# cc2530.net
KiCad netlist of a schematic drawn in Altium Designer
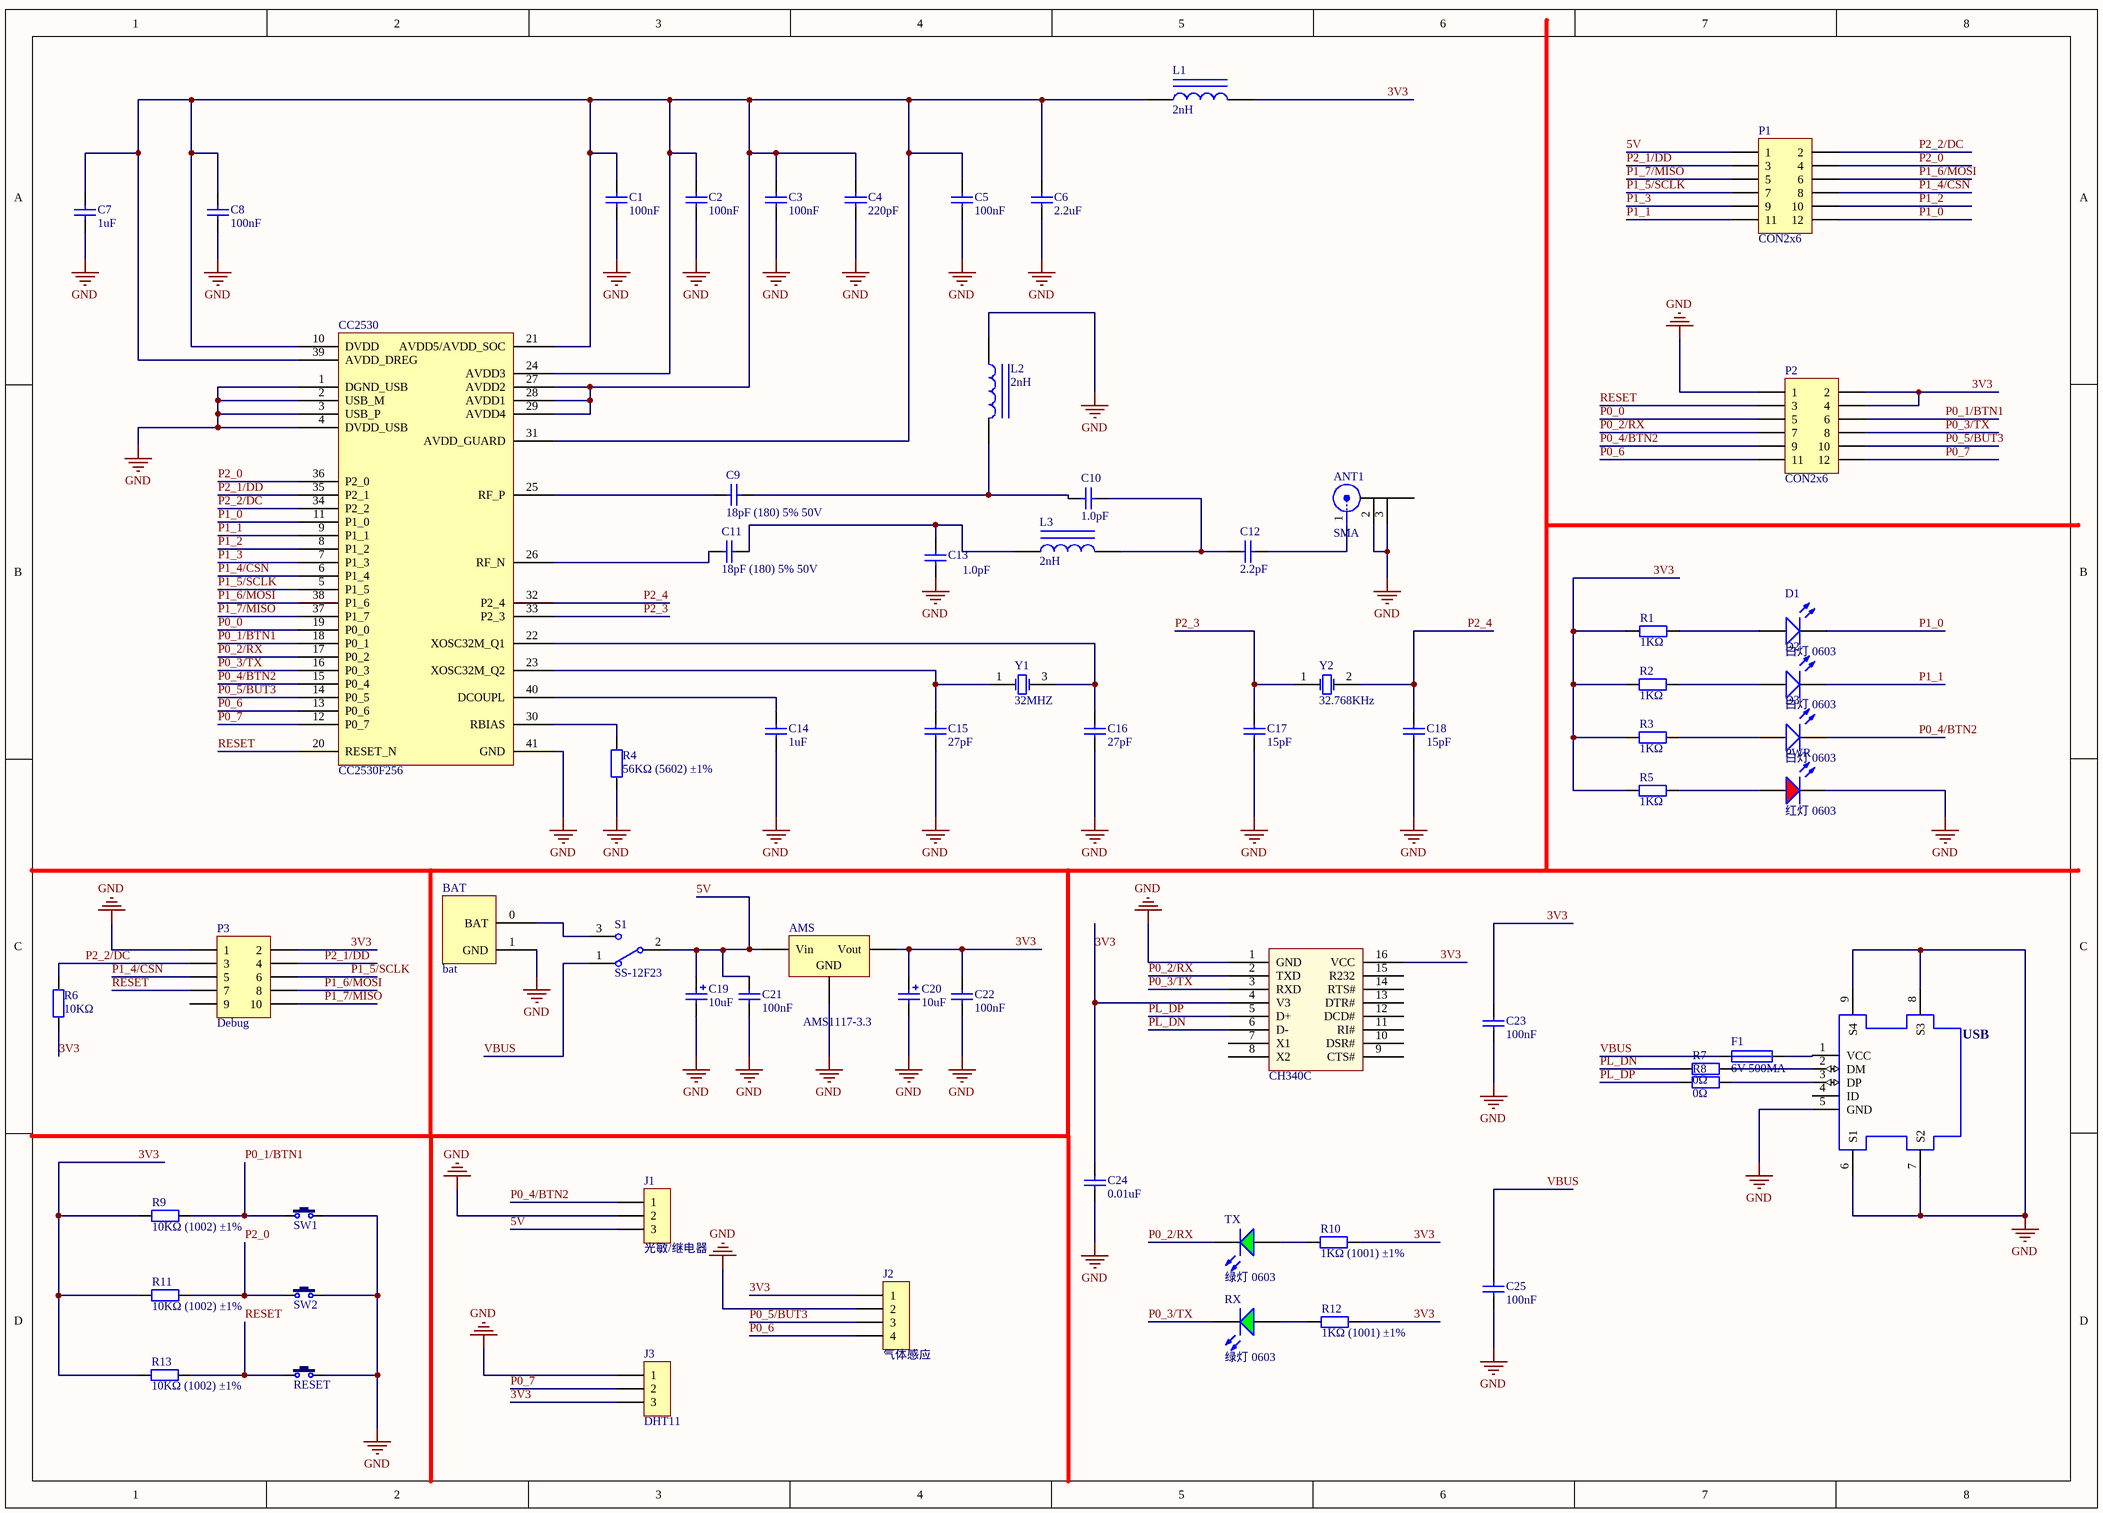
[diagram p0: cc2530.SchDoc]

(export (version "E")
  (design (tool "Eeschema 10.0.6"))
  (components
    (comp (ref "AMS")
      (value "AMS1117-3.3")
      (footprint "SOT-223")
      (description "低压差线性稳压(LDO)")
      (libsource (lib "Miscellaneous Devices LC") (part "SOT-223 AMS1117-3.3"))
    )
    (comp (ref "ANT1") (value "SMA") (footprint "SMA-KE") (libsource (lib "2530核心板原理图库") (part "SMA")))
    (comp (ref "BAT") (value "bat") (footprint "BAT") (libsource (lib "2530底板原理图库") (part "bat")))
    (comp (ref "C1")
      (value "100nF")
      (footprint "0603_C")
      (description "贴片电容")
      (libsource (lib "Miscellaneous Devices LC") (part "0603 100nF (104) 10% 50V"))
    )
    (comp (ref "C2")
      (value "100nF")
      (footprint "0603_C")
      (description "贴片电容")
      (libsource (lib "Miscellaneous Devices LC") (part "0603 100nF (104) 10% 50V"))
    )
    (comp (ref "C3")
      (value "100nF")
      (footprint "0603_C")
      (description "贴片电容")
      (libsource (lib "Miscellaneous Devices LC") (part "0603 100nF (104) 10% 50V"))
    )
    (comp (ref "C4")
      (value "220pF")
      (footprint "0603_C")
      (description "贴片电容")
      (libsource (lib "Miscellaneous Devices LC") (part "0603 220pF (221) 10% 50V"))
    )
    (comp (ref "C5")
      (value "100nF")
      (footprint "0603_C")
      (description "贴片电容")
      (libsource (lib "Miscellaneous Devices LC") (part "0603 100nF (104) 10% 50V"))
    )
    (comp (ref "C6")
      (value "2.2uF")
      (footprint "0603_C")
      (description "贴片电容")
      (libsource (lib "Miscellaneous Devices LC") (part "0603 2.2uF (225) 10% 16V"))
    )
    (comp (ref "C7")
      (value "1uF")
      (footprint "0603_C")
      (description "贴片电容")
      (libsource (lib "Miscellaneous Devices LC") (part "0603 1uF (105) 10% 50V"))
    )
    (comp (ref "C8")
      (value "100nF")
      (footprint "0603_C")
      (description "贴片电容")
      (libsource (lib "Miscellaneous Devices LC") (part "0603 100nF (104) 10% 50V"))
    )
    (comp (ref "C9")
      (value "18pF (180) 5% 50V")
      (footprint "0603_C")
      (description "贴片电容")
      (libsource (lib "Miscellaneous Devices LC") (part "0603 18pF (180) 5% 50V"))
    )
    (comp (ref "C10")
      (value "1.0pF")
      (footprint "0805_C")
      (description "贴片电容")
      (libsource (lib "Miscellaneous Devices LC") (part "0805 1.0pF (010) 0.25pF 50V"))
    )
    (comp (ref "C11")
      (value "18pF (180) 5% 50V")
      (footprint "0603_C")
      (description "贴片电容")
      (libsource (lib "Miscellaneous Devices LC") (part "0603 18pF (180) 5% 50V"))
    )
    (comp (ref "C12")
      (value "2.2pF")
      (footprint "0603_C")
      (description "贴片电容")
      (libsource (lib "Miscellaneous Devices LC") (part "0603 2.2uF (225) 10% 16V"))
    )
    (comp (ref "C13")
      (value "1.0pF")
      (footprint "0805_C")
      (description "贴片电容")
      (libsource (lib "Miscellaneous Devices LC") (part "0805 1.0pF (010) 0.25pF 50V"))
    )
    (comp (ref "C14")
      (value "1uF")
      (footprint "0603_C")
      (description "贴片电容")
      (libsource (lib "Miscellaneous Devices LC") (part "0603 100nF (104) 10% 50V"))
    )
    (comp (ref "C15")
      (value "27pF")
      (footprint "0603_C")
      (description "贴片电容")
      (libsource (lib "Miscellaneous Devices LC") (part "0603 100nF (104) 10% 50V"))
    )
    (comp (ref "C16")
      (value "27pF")
      (footprint "0603_C")
      (description "贴片电容")
      (libsource (lib "Miscellaneous Devices LC") (part "0603 100nF (104) 10% 50V"))
    )
    (comp (ref "C17")
      (value "15pF")
      (footprint "0603_C")
      (description "贴片电容")
      (libsource (lib "Miscellaneous Devices LC") (part "0603 100nF (104) 10% 50V"))
    )
    (comp (ref "C18")
      (value "15pF")
      (footprint "0603_C")
      (description "贴片电容")
      (libsource (lib "Miscellaneous Devices LC") (part "0603 100nF (104) 10% 50V"))
    )
    (comp (ref "C19")
      (value "10uF")
      (footprint "CASE-A_3216")
      (description "钽电容")
      (libsource (lib "Miscellaneous Devices LC") (part "3216 10uF (106) 10% 16V"))
    )
    (comp (ref "C20")
      (value "10uF")
      (footprint "CASE-A_3216")
      (description "钽电容")
      (libsource (lib "Miscellaneous Devices LC") (part "3216 10uF (106) 10% 16V"))
    )
    (comp (ref "C21")
      (value "100nF")
      (footprint "0603_C")
      (description "贴片电容")
      (libsource (lib "Miscellaneous Devices LC") (part "0603 100nF (104) 10% 50V"))
    )
    (comp (ref "C22")
      (value "100nF")
      (footprint "0603_C")
      (description "贴片电容")
      (libsource (lib "Miscellaneous Devices LC") (part "0603 100nF (104) 10% 50V"))
    )
    (comp (ref "C23")
      (value "100nF")
      (footprint "0603_C")
      (description "贴片电容")
      (libsource (lib "Miscellaneous Devices LC") (part "0603 100nF (104) 10% 50V"))
    )
    (comp (ref "C24")
      (value "0.01uF")
      (footprint "0603_C")
      (description "贴片电容")
      (libsource (lib "Miscellaneous Devices LC") (part "0603 100nF (104) 10% 50V"))
    )
    (comp (ref "C25")
      (value "100nF")
      (footprint "0603_C")
      (description "贴片电容")
      (libsource (lib "Miscellaneous Devices LC") (part "0603 100nF (104) 10% 50V"))
    )
    (comp (ref "CC2530")
      (value "CC2530F256")
      (footprint "PVQFN-N40")
      (libsource (lib "2530核心板原理图库") (part "CC2530"))
    )
    (comp (ref "CH340C")
      (value "CH340C")
      (footprint "SOIC-16_150mil")
      (libsource (lib "1.9 - CH340系列编程器芯片") (part "CH340C"))
    )
    (comp (ref "D1")
      (value "白灯 0603")
      (footprint "0603_LED_S1")
      (description "发光二极管")
      (libsource (lib "Miscellaneous Devices LC") (part "0603 白灯"))
    )
    (comp (ref "D2")
      (value "白灯 0603")
      (footprint "0603_LED_S1")
      (description "发光二极管")
      (libsource (lib "Miscellaneous Devices LC") (part "0603 白灯"))
    )
    (comp (ref "D3")
      (value "白灯 0603")
      (footprint "0603_LED_S1")
      (description "发光二极管")
      (libsource (lib "Miscellaneous Devices LC") (part "0603 白灯"))
    )
    (comp (ref "F1")
      (value "6V 500MA")
      (footprint "0805")
      (description "保险丝")
      (libsource (lib "Component") (part "FUSE"))
    )
    (comp (ref "J1")
      (value "光敏/继电器")
      (footprint "HDR1X3")
      (description "连接器")
      (libsource (lib "Connector") (part "CON3"))
    )
    (comp (ref "J2")
      (value "气体感应")
      (footprint "HDR1X4")
      (description "连接器")
      (libsource (lib "Connector") (part "CON4"))
    )
    (comp (ref "J3")
      (value "DHT11")
      (footprint "HDR1X3")
      (description "连接器")
      (libsource (lib "Connector") (part "CON3"))
    )
    (comp (ref "L1")
      (value "2nH")
      (footprint "0402_L")
      (description "贴片电感")
      (libsource (lib "Miscellaneous Devices LC") (part "0402 2.7nH 0.3nH"))
    )
    (comp (ref "L2")
      (value "2nH")
      (footprint "0402_L")
      (description "贴片电感")
      (libsource (lib "Miscellaneous Devices LC") (part "0402 2.7nH 0.3nH"))
    )
    (comp (ref "L3")
      (value "2nH")
      (footprint "0402_L")
      (description "贴片电感")
      (libsource (lib "Miscellaneous Devices LC") (part "0402 2.7nH 0.3nH"))
    )
    (comp (ref "P1")
      (value "CON2x6")
      (footprint "2530底板PCB库:CON2X6")
      (libsource (lib "2530底板原理图库") (part "CON2x6"))
    )
    (comp (ref "P2")
      (value "CON2x6")
      (footprint "2530底板PCB库:CON2X6")
      (libsource (lib "2530底板原理图库") (part "CON2x6"))
    )
    (comp (ref "P3")
      (value "Debug")
      (footprint "DEBUG10")
      (description "Header, 5-Pin, Dual row")
      (libsource (lib "2530底板原理图库") (part "Header 5X2"))
    )
    (comp (ref "PWR")
      (value "红灯 0603")
      (footprint "0603_LED_S1")
      (description "发光二极管")
      (libsource (lib "Miscellaneous Devices LC") (part "0603 红灯"))
    )
    (comp (ref "R1")
      (value "1KΩ")
      (footprint "0603_R")
      (description "贴片电阻")
      (libsource (lib "Miscellaneous Devices LC") (part "0603 1.1KΩ (1101) 1%"))
    )
    (comp (ref "R2")
      (value "1KΩ")
      (footprint "0603_R")
      (description "贴片电阻")
      (libsource (lib "Miscellaneous Devices LC") (part "0603 1.1KΩ (1101) 1%"))
    )
    (comp (ref "R3")
      (value "1KΩ")
      (footprint "0603_R")
      (description "贴片电阻")
      (libsource (lib "Miscellaneous Devices LC") (part "0603 1.1KΩ (1101) 1%"))
    )
    (comp (ref "R4")
      (value "56KΩ (5602) ±1%")
      (footprint "0603_R")
      (description "贴片电阻")
      (libsource (lib "Miscellaneous Devices LC") (part "0603 56KΩ (5602) 1%"))
    )
    (comp (ref "R5")
      (value "1KΩ")
      (footprint "0603_R")
      (description "贴片电阻")
      (libsource (lib "Miscellaneous Devices LC") (part "0603 1.1KΩ (1101) 1%"))
    )
    (comp (ref "R6")
      (value "10KΩ")
      (footprint "0603_R")
      (description "贴片电阻")
      (libsource (lib "") (part "0603 10KΩ (1002) 1%_1"))
    )
    (comp (ref "R7")
      (value "0Ω")
      (footprint "0603_R")
      (description "贴片电阻")
      (libsource (lib "Miscellaneous Devices LC") (part "0603 0Ω (0R0) 1%"))
    )
    (comp (ref "R8")
      (value "0Ω")
      (footprint "0603_R")
      (description "贴片电阻")
      (libsource (lib "Miscellaneous Devices LC") (part "0603 0Ω (0R0) 1%"))
    )
    (comp (ref "R9")
      (value "10KΩ (1002) ±1%")
      (footprint "0603_R")
      (description "贴片电阻")
      (libsource (lib "Miscellaneous Devices LC") (part "0603 10KΩ (1002) 1%"))
    )
    (comp (ref "R10")
      (value "1KΩ (1001) ±1%")
      (footprint "0603_R")
      (description "贴片电阻")
      (libsource (lib "Miscellaneous Devices LC") (part "0603 1KΩ (1001) 1%"))
    )
    (comp (ref "R11")
      (value "10KΩ (1002) ±1%")
      (footprint "0603_R")
      (description "贴片电阻")
      (libsource (lib "Miscellaneous Devices LC") (part "0603 10KΩ (1002) 1%"))
    )
    (comp (ref "R12")
      (value "1KΩ (1001) ±1%")
      (footprint "0603_R")
      (description "贴片电阻")
      (libsource (lib "Miscellaneous Devices LC") (part "0603 1KΩ (1001) 1%"))
    )
    (comp (ref "R13")
      (value "10KΩ (1002) ±1%")
      (footprint "0603_R")
      (description "贴片电阻")
      (libsource (lib "Miscellaneous Devices LC") (part "0603 10KΩ (1002) 1%"))
    )
    (comp (ref "RESET")
      (value "6x6x5")
      (footprint "TSW SMD-3*6*2.5")
      (description "侧按直插6x6轻触开关")
      (fields (field (name "版权归属") "封装库来自淘宝 ID：黄晶宝石"))
      (libsource (lib "0.7 - 常用按键-开关") (part "TSW DIP-6x6_V"))
    )
    (comp (ref "RX")
      (value "绿灯 0603")
      (footprint "0603_LED_S1")
      (description "发光二极管")
      (libsource (lib "Miscellaneous Devices LC") (part "0603 绿灯"))
    )
    (comp (ref "S1")
      (value "SS-12F23")
      (footprint "SS-12F23")
      (description "1路波动开关")
      (fields (field (name "版权归属") "封装库来自淘宝 ID：黄晶宝石"))
      (libsource (lib "0.7 - 常用按键-开关") (part "SSW-1P"))
    )
    (comp (ref "SW1")
      (value "6x6x5")
      (footprint "TSW SMD-3*6*2.5")
      (description "侧按直插6x6轻触开关")
      (fields (field (name "版权归属") "封装库来自淘宝 ID：黄晶宝石"))
      (libsource (lib "0.7 - 常用按键-开关") (part "TSW DIP-6x6_V"))
    )
    (comp (ref "SW2")
      (value "6x6x5")
      (footprint "TSW SMD-3*6*2.5")
      (description "侧按直插6x6轻触开关")
      (fields (field (name "版权归属") "封装库来自淘宝 ID：黄晶宝石"))
      (libsource (lib "0.7 - 常用按键-开关") (part "TSW DIP-6x6_V"))
    )
    (comp (ref "TX")
      (value "绿灯 0603")
      (footprint "0603_LED_S1")
      (description "发光二极管")
      (libsource (lib "Miscellaneous Devices LC") (part "0603 绿灯"))
    )
    (comp (ref "USB")
      (value "Mini USB")
      (footprint "SMT-MINI USB")
      (description "IC")
      (fields
        (field (name "MANUFACTURER PART NUMBER") "USB Plug P/N: MUSB-B5-S-VT-02")
        (field (name "PUBLISHER1") "Stephen Lui")
        (field (name "PUBLISHER2") "Tianshen")
      )
      (libsource (lib "2530底板原理图库") (part "USB-1"))
    )
    (comp (ref "Y1")
      (value "32MHZ")
      (footprint "SMD-3225_4P")
      (description "贴片晶振")
      (libsource (lib "Miscellaneous Devices LC") (part "SMD-3225_4P  25MHZ 12PF 10PPM"))
    )
    (comp (ref "Y2")
      (value "32.768KHz")
      (footprint "SMD-3215_2P FC - 135")
      (description "贴片晶振")
      (libsource (lib "Miscellaneous Devices LC") (part "SMD-3215_2P 32.768KHz 20ppm 12.5pF"))
    )
  )
  (nets
    (net (code "1") (name "/3V3") (class "Default")
      (node (ref "AMS") (pin "2") (pinfunction "Vout_2") (pintype "passive"))
      (node (ref "C20") (pin "1") (pinfunction "1_1") (pintype "passive"))
      (node (ref "C22") (pin "2") (pinfunction "2_2") (pintype "passive"))
      (node (ref "C23") (pin "2") (pinfunction "2_2") (pintype "passive"))
      (node (ref "C24") (pin "2") (pinfunction "2_2") (pintype "passive"))
      (node (ref "CH340C") (pin "16") (pinfunction "VCC_16") (pintype "passive"))
      (node (ref "CH340C") (pin "4") (pinfunction "V3_4") (pintype "passive"))
      (node (ref "J2") (pin "1") (pinfunction "1_1") (pintype "passive"))
      (node (ref "J3") (pin "3") (pinfunction "3_3") (pintype "passive"))
      (node (ref "L1") (pin "2") (pinfunction "2_2") (pintype "passive"))
      (node (ref "P2") (pin "2") (pinfunction "2_2") (pintype "passive"))
      (node (ref "P2") (pin "4") (pinfunction "4_4") (pintype "passive"))
      (node (ref "P3") (pin "2") (pinfunction "2_2") (pintype "passive"))
      (node (ref "R1") (pin "1") (pinfunction "1_1") (pintype "passive"))
      (node (ref "R10") (pin "2") (pinfunction "2_2") (pintype "passive"))
      (node (ref "R11") (pin "1") (pinfunction "1_1") (pintype "passive"))
      (node (ref "R12") (pin "2") (pinfunction "2_2") (pintype "passive"))
      (node (ref "R13") (pin "1") (pinfunction "1_1") (pintype "passive"))
      (node (ref "R2") (pin "1") (pinfunction "1_1") (pintype "passive"))
      (node (ref "R3") (pin "1") (pinfunction "1_1") (pintype "passive"))
      (node (ref "R5") (pin "1") (pinfunction "1_1") (pintype "passive"))
      (node (ref "R6") (pin "1") (pinfunction "1_1") (pintype "passive"))
      (node (ref "R9") (pin "1") (pinfunction "1_1") (pintype "passive"))
    )
    (net (code "2") (name "/5V") (class "Default")
      (node (ref "AMS") (pin "3") (pinfunction "Vin_3") (pintype "passive"))
      (node (ref "C19") (pin "1") (pinfunction "1_1") (pintype "passive"))
      (node (ref "C21") (pin "2") (pinfunction "2_2") (pintype "passive"))
      (node (ref "J1") (pin "3") (pinfunction "3_3") (pintype "passive"))
      (node (ref "P1") (pin "1") (pinfunction "1_1") (pintype "passive"))
      (node (ref "S1") (pin "2") (pinfunction "2_2") (pintype "passive"))
    )
    (net (code "3") (name "/P0_0") (class "Default")
      (node (ref "CC2530") (pin "19") (pinfunction "P0_0_19") (pintype "passive"))
      (node (ref "P2") (pin "5") (pinfunction "5_5") (pintype "passive"))
    )
    (net (code "4") (name "/P0_1{slash}BTN1") (class "Default")
      (node (ref "CC2530") (pin "18") (pinfunction "P0_1_18") (pintype "passive"))
      (node (ref "P2") (pin "6") (pinfunction "6_6") (pintype "passive"))
      (node (ref "R9") (pin "2") (pinfunction "2_2") (pintype "passive"))
      (node (ref "SW1") (pin "1") (pinfunction "1_1") (pintype "passive"))
    )
    (net (code "5") (name "/P0_2{slash}RX") (class "Default")
      (node (ref "CC2530") (pin "17") (pinfunction "P0_2_17") (pintype "passive"))
      (node (ref "CH340C") (pin "2") (pinfunction "TXD_2") (pintype "passive"))
      (node (ref "P2") (pin "7") (pinfunction "7_7") (pintype "passive"))
      (node (ref "TX") (pin "K") (pinfunction "K_K") (pintype "passive"))
    )
    (net (code "6") (name "/P0_3{slash}TX") (class "Default")
      (node (ref "CC2530") (pin "16") (pinfunction "P0_3_16") (pintype "passive"))
      (node (ref "CH340C") (pin "3") (pinfunction "RXD_3") (pintype "passive"))
      (node (ref "P2") (pin "8") (pinfunction "8_8") (pintype "passive"))
      (node (ref "RX") (pin "K") (pinfunction "K_K") (pintype "passive"))
    )
    (net (code "7") (name "/P0_4{slash}BTN2") (class "Default")
      (node (ref "CC2530") (pin "15") (pinfunction "P0_4_15") (pintype "passive"))
      (node (ref "D3") (pin "K") (pinfunction "K_K") (pintype "passive"))
      (node (ref "J1") (pin "1") (pinfunction "1_1") (pintype "passive"))
      (node (ref "P2") (pin "9") (pinfunction "9_9") (pintype "passive"))
    )
    (net (code "8") (name "/P0_5{slash}BUT3") (class "Default")
      (node (ref "CC2530") (pin "14") (pinfunction "P0_5_14") (pintype "passive"))
      (node (ref "J2") (pin "3") (pinfunction "3_3") (pintype "passive"))
      (node (ref "P2") (pin "10") (pinfunction "10_10") (pintype "passive"))
    )
    (net (code "9") (name "/P0_6") (class "Default")
      (node (ref "CC2530") (pin "13") (pinfunction "P0_6_13") (pintype "passive"))
      (node (ref "J2") (pin "4") (pinfunction "4_4") (pintype "passive"))
      (node (ref "P2") (pin "11") (pinfunction "11_11") (pintype "passive"))
    )
    (net (code "10") (name "/P0_7") (class "Default")
      (node (ref "CC2530") (pin "12") (pinfunction "P0_7_12") (pintype "passive"))
      (node (ref "J3") (pin "2") (pinfunction "2_2") (pintype "passive"))
      (node (ref "P2") (pin "12") (pinfunction "12_12") (pintype "passive"))
    )
    (net (code "11") (name "/P1_0") (class "Default")
      (node (ref "CC2530") (pin "11") (pinfunction "P1_0_11") (pintype "passive"))
      (node (ref "D1") (pin "K") (pinfunction "K_K") (pintype "passive"))
      (node (ref "P1") (pin "12") (pinfunction "12_12") (pintype "passive"))
    )
    (net (code "12") (name "/P1_1") (class "Default")
      (node (ref "CC2530") (pin "9") (pinfunction "P1_1_9") (pintype "passive"))
      (node (ref "D2") (pin "K") (pinfunction "K_K") (pintype "passive"))
      (node (ref "P1") (pin "11") (pinfunction "11_11") (pintype "passive"))
    )
    (net (code "13") (name "/P1_2") (class "Default")
      (node (ref "CC2530") (pin "8") (pinfunction "P1_2_8") (pintype "passive"))
      (node (ref "P1") (pin "10") (pinfunction "10_10") (pintype "passive"))
    )
    (net (code "14") (name "/P1_3") (class "Default")
      (node (ref "CC2530") (pin "7") (pinfunction "P1_3_7") (pintype "passive"))
      (node (ref "P1") (pin "9") (pinfunction "9_9") (pintype "passive"))
    )
    (net (code "15") (name "/P1_4{slash}CSN") (class "Default")
      (node (ref "CC2530") (pin "6") (pinfunction "P1_4_6") (pintype "passive"))
      (node (ref "P1") (pin "8") (pinfunction "8_8") (pintype "passive"))
      (node (ref "P3") (pin "5") (pinfunction "5_5") (pintype "passive"))
    )
    (net (code "16") (name "/P1_5{slash}SCLK") (class "Default")
      (node (ref "CC2530") (pin "5") (pinfunction "P1_5_5") (pintype "passive"))
      (node (ref "P1") (pin "7") (pinfunction "7_7") (pintype "passive"))
      (node (ref "P3") (pin "6") (pinfunction "6_6") (pintype "passive"))
    )
    (net (code "17") (name "/P1_6{slash}MOSI") (class "Default")
      (node (ref "CC2530") (pin "38") (pinfunction "P1_6_38") (pintype "passive"))
      (node (ref "P1") (pin "6") (pinfunction "6_6") (pintype "passive"))
      (node (ref "P3") (pin "8") (pinfunction "8_8") (pintype "passive"))
    )
    (net (code "18") (name "/P1_7{slash}MISO") (class "Default")
      (node (ref "CC2530") (pin "37") (pinfunction "P1_7_37") (pintype "passive"))
      (node (ref "P1") (pin "5") (pinfunction "5_5") (pintype "passive"))
      (node (ref "P3") (pin "10") (pinfunction "10_10") (pintype "passive"))
    )
    (net (code "19") (name "/P2_0") (class "Default")
      (node (ref "CC2530") (pin "36") (pinfunction "P2_0_36") (pintype "passive"))
      (node (ref "P1") (pin "4") (pinfunction "4_4") (pintype "passive"))
      (node (ref "R11") (pin "2") (pinfunction "2_2") (pintype "passive"))
      (node (ref "SW2") (pin "1") (pinfunction "1_1") (pintype "passive"))
    )
    (net (code "20") (name "/P2_1{slash}DD") (class "Default")
      (node (ref "CC2530") (pin "35") (pinfunction "P2_1_35") (pintype "passive"))
      (node (ref "P1") (pin "3") (pinfunction "3_3") (pintype "passive"))
      (node (ref "P3") (pin "4") (pinfunction "4_4") (pintype "passive"))
    )
    (net (code "21") (name "/P2_2{slash}DC") (class "Default")
      (node (ref "CC2530") (pin "34") (pinfunction "P2_2_34") (pintype "passive"))
      (node (ref "P1") (pin "2") (pinfunction "2_2") (pintype "passive"))
      (node (ref "P3") (pin "3") (pinfunction "3_3") (pintype "passive"))
      (node (ref "R6") (pin "2") (pinfunction "2_2") (pintype "passive"))
    )
    (net (code "22") (name "/P2_3") (class "Default")
      (node (ref "C17") (pin "2") (pinfunction "2_2") (pintype "passive"))
      (node (ref "CC2530") (pin "33") (pinfunction "P2_3_33") (pintype "passive"))
      (node (ref "Y2") (pin "1") (pinfunction "OSC1_1") (pintype "passive"))
    )
    (net (code "23") (name "/P2_4") (class "Default")
      (node (ref "C18") (pin "2") (pinfunction "2_2") (pintype "passive"))
      (node (ref "CC2530") (pin "32") (pinfunction "P2_4_32") (pintype "passive"))
      (node (ref "Y2") (pin "2") (pinfunction "OSC2_2") (pintype "passive"))
    )
    (net (code "24") (name "/PL_DN") (class "Default")
      (node (ref "CH340C") (pin "6") (pinfunction "D-_6") (pintype "passive"))
      (node (ref "R7") (pin "1") (pinfunction "1_1") (pintype "passive"))
    )
    (net (code "25") (name "/PL_DP") (class "Default")
      (node (ref "CH340C") (pin "5") (pinfunction "D+_5") (pintype "passive"))
      (node (ref "R8") (pin "1") (pinfunction "1_1") (pintype "passive"))
    )
    (net (code "26") (name "/RESET") (class "Default")
      (node (ref "CC2530") (pin "20") (pinfunction "RESET_N_20") (pintype "passive"))
      (node (ref "P2") (pin "3") (pinfunction "3_3") (pintype "passive"))
      (node (ref "P3") (pin "7") (pinfunction "7_7") (pintype "passive"))
      (node (ref "R13") (pin "2") (pinfunction "2_2") (pintype "passive"))
      (node (ref "RESET") (pin "1") (pinfunction "1_1") (pintype "passive"))
    )
    (net (code "27") (name "/VBUS") (class "Default")
      (node (ref "C25") (pin "2") (pinfunction "2_2") (pintype "passive"))
      (node (ref "F1") (pin "1") (pinfunction "1_1") (pintype "passive"))
      (node (ref "S1") (pin "1") (pinfunction "1_1") (pintype "passive"))
    )
    (net (code "28") (name "GND") (class "Default")
      (node (ref "AMS") (pin "1") (pinfunction "GND_1") (pintype "passive"))
      (node (ref "ANT1") (pin "2") (pinfunction "2_2") (pintype "passive"))
      (node (ref "ANT1") (pin "3") (pinfunction "3_3") (pintype "passive"))
      (node (ref "BAT") (pin "1") (pinfunction "GND_1") (pintype "passive"))
      (node (ref "C1") (pin "1") (pinfunction "1_1") (pintype "passive"))
      (node (ref "C13") (pin "1") (pinfunction "1_1") (pintype "passive"))
      (node (ref "C14") (pin "1") (pinfunction "1_1") (pintype "passive"))
      (node (ref "C15") (pin "1") (pinfunction "1_1") (pintype "passive"))
      (node (ref "C16") (pin "1") (pinfunction "1_1") (pintype "passive"))
      (node (ref "C17") (pin "1") (pinfunction "1_1") (pintype "passive"))
      (node (ref "C18") (pin "1") (pinfunction "1_1") (pintype "passive"))
      (node (ref "C19") (pin "2") (pinfunction "2_2") (pintype "passive"))
      (node (ref "C2") (pin "1") (pinfunction "1_1") (pintype "passive"))
      (node (ref "C20") (pin "2") (pinfunction "2_2") (pintype "passive"))
      (node (ref "C21") (pin "1") (pinfunction "1_1") (pintype "passive"))
      (node (ref "C22") (pin "1") (pinfunction "1_1") (pintype "passive"))
      (node (ref "C23") (pin "1") (pinfunction "1_1") (pintype "passive"))
      (node (ref "C24") (pin "1") (pinfunction "1_1") (pintype "passive"))
      (node (ref "C25") (pin "1") (pinfunction "1_1") (pintype "passive"))
      (node (ref "C3") (pin "1") (pinfunction "1_1") (pintype "passive"))
      (node (ref "C4") (pin "1") (pinfunction "1_1") (pintype "passive"))
      (node (ref "C5") (pin "1") (pinfunction "1_1") (pintype "passive"))
      (node (ref "C6") (pin "1") (pinfunction "1_1") (pintype "passive"))
      (node (ref "C7") (pin "1") (pinfunction "1_1") (pintype "passive"))
      (node (ref "C8") (pin "1") (pinfunction "1_1") (pintype "passive"))
      (node (ref "CC2530") (pin "1") (pinfunction "DGND_USB_1") (pintype "passive"))
      (node (ref "CC2530") (pin "2") (pinfunction "USB_M_2") (pintype "passive"))
      (node (ref "CC2530") (pin "3") (pinfunction "USB_P_3") (pintype "passive"))
      (node (ref "CC2530") (pin "4") (pinfunction "DVDD_USB_4") (pintype "passive"))
      (node (ref "CC2530") (pin "41") (pinfunction "GND_41") (pintype "passive"))
      (node (ref "CH340C") (pin "1") (pinfunction "GND_1") (pintype "passive"))
      (node (ref "J1") (pin "2") (pinfunction "2_2") (pintype "passive"))
      (node (ref "J2") (pin "2") (pinfunction "2_2") (pintype "passive"))
      (node (ref "J3") (pin "1") (pinfunction "1_1") (pintype "passive"))
      (node (ref "L2") (pin "1") (pinfunction "1_1") (pintype "passive"))
      (node (ref "P2") (pin "1") (pinfunction "1_1") (pintype "passive"))
      (node (ref "P3") (pin "1") (pinfunction "1_1") (pintype "passive"))
      (node (ref "PWR") (pin "K") (pinfunction "K_K") (pintype "passive"))
      (node (ref "R4") (pin "1") (pinfunction "1_1") (pintype "passive"))
      (node (ref "RESET") (pin "2") (pinfunction "2_2") (pintype "passive"))
      (node (ref "SW1") (pin "2") (pinfunction "2_2") (pintype "passive"))
      (node (ref "SW2") (pin "2") (pinfunction "2_2") (pintype "passive"))
      (node (ref "USB") (pin "5") (pinfunction "GND_5") (pintype "passive"))
      (node (ref "USB") (pin "6") (pinfunction "S1_6") (pintype "passive"))
      (node (ref "USB") (pin "7") (pinfunction "S2_7") (pintype "passive"))
      (node (ref "USB") (pin "8") (pinfunction "S3_8") (pintype "passive"))
      (node (ref "USB") (pin "9") (pinfunction "S4_9") (pintype "passive"))
    )
    (net (code "29") (name "Net-(ANT1-Pad1)") (class "Default")
      (node (ref "ANT1") (pin "1") (pinfunction "1_1") (pintype "passive"))
      (node (ref "C12") (pin "2") (pinfunction "2_2") (pintype "passive"))
    )
    (net (code "30") (name "Net-(BAT-BAT)") (class "Default")
      (node (ref "BAT") (pin "0") (pinfunction "BAT_0") (pintype "passive"))
      (node (ref "S1") (pin "3") (pinfunction "3_3") (pintype "passive"))
    )
    (net (code "31") (name "Net-(C10-Pad1)") (class "Default")
      (node (ref "C10") (pin "1") (pinfunction "1_1") (pintype "passive"))
      (node (ref "C9") (pin "2") (pinfunction "2_2") (pintype "passive"))
      (node (ref "L2") (pin "2") (pinfunction "2_2") (pintype "passive"))
    )
    (net (code "32") (name "Net-(C10-Pad2)") (class "Default")
      (node (ref "C10") (pin "2") (pinfunction "2_2") (pintype "passive"))
      (node (ref "C12") (pin "1") (pinfunction "1_1") (pintype "passive"))
      (node (ref "L3") (pin "2") (pinfunction "2_2") (pintype "passive"))
    )
    (net (code "33") (name "Net-(C11-Pad2)") (class "Default")
      (node (ref "C11") (pin "2") (pinfunction "2_2") (pintype "passive"))
      (node (ref "C13") (pin "2") (pinfunction "2_2") (pintype "passive"))
      (node (ref "L3") (pin "1") (pinfunction "1_1") (pintype "passive"))
    )
    (net (code "34") (name "Net-(CC2530-AVDD1)") (class "Default")
      (node (ref "C1") (pin "2") (pinfunction "2_2") (pintype "passive"))
      (node (ref "C2") (pin "2") (pinfunction "2_2") (pintype "passive"))
      (node (ref "C3") (pin "2") (pinfunction "2_2") (pintype "passive"))
      (node (ref "C4") (pin "2") (pinfunction "2_2") (pintype "passive"))
      (node (ref "C5") (pin "2") (pinfunction "2_2") (pintype "passive"))
      (node (ref "C6") (pin "2") (pinfunction "2_2") (pintype "passive"))
      (node (ref "C7") (pin "2") (pinfunction "2_2") (pintype "passive"))
      (node (ref "C8") (pin "2") (pinfunction "2_2") (pintype "passive"))
      (node (ref "CC2530") (pin "10") (pinfunction "DVDD_10") (pintype "passive"))
      (node (ref "CC2530") (pin "21") (pinfunction "AVDD5/AVDD_SOC_21") (pintype "passive"))
      (node (ref "CC2530") (pin "24") (pinfunction "AVDD3_24") (pintype "passive"))
      (node (ref "CC2530") (pin "27") (pinfunction "AVDD2_27") (pintype "passive"))
      (node (ref "CC2530") (pin "28") (pinfunction "AVDD1_28") (pintype "passive"))
      (node (ref "CC2530") (pin "29") (pinfunction "AVDD4_29") (pintype "passive"))
      (node (ref "CC2530") (pin "31") (pinfunction "AVDD_GUARD_31") (pintype "passive"))
      (node (ref "CC2530") (pin "39") (pinfunction "AVDD_DREG_39") (pintype "passive"))
      (node (ref "L1") (pin "1") (pinfunction "1_1") (pintype "passive"))
    )
    (net (code "35") (name "Net-(CC2530-DCOUPL)") (class "Default")
      (node (ref "C14") (pin "2") (pinfunction "2_2") (pintype "passive"))
      (node (ref "CC2530") (pin "40") (pinfunction "DCOUPL_40") (pintype "passive"))
    )
    (net (code "36") (name "Net-(CC2530-RBIAS)") (class "Default")
      (node (ref "CC2530") (pin "30") (pinfunction "RBIAS_30") (pintype "passive"))
      (node (ref "R4") (pin "2") (pinfunction "2_2") (pintype "passive"))
    )
    (net (code "37") (name "Net-(CC2530-RF_N)") (class "Default")
      (node (ref "C11") (pin "1") (pinfunction "1_1") (pintype "passive"))
      (node (ref "CC2530") (pin "26") (pinfunction "RF_N_26") (pintype "passive"))
    )
    (net (code "38") (name "Net-(CC2530-RF_P)") (class "Default")
      (node (ref "C9") (pin "1") (pinfunction "1_1") (pintype "passive"))
      (node (ref "CC2530") (pin "25") (pinfunction "RF_P_25") (pintype "passive"))
    )
    (net (code "39") (name "Net-(CC2530-XOSC32M_Q1)") (class "Default")
      (node (ref "C16") (pin "2") (pinfunction "2_2") (pintype "passive"))
      (node (ref "CC2530") (pin "22") (pinfunction "XOSC32M_Q1_22") (pintype "passive"))
      (node (ref "Y1") (pin "3") (pinfunction "OSC2_3") (pintype "passive"))
    )
    (net (code "40") (name "Net-(CC2530-XOSC32M_Q2)") (class "Default")
      (node (ref "C15") (pin "2") (pinfunction "2_2") (pintype "passive"))
      (node (ref "CC2530") (pin "23") (pinfunction "XOSC32M_Q2_23") (pintype "passive"))
      (node (ref "Y1") (pin "1") (pinfunction "OSC1_1") (pintype "passive"))
    )
    (net (code "41") (name "Net-(D1-PadA)") (class "Default")
      (node (ref "D1") (pin "A") (pinfunction "A_A") (pintype "passive"))
      (node (ref "R1") (pin "2") (pinfunction "2_2") (pintype "passive"))
    )
    (net (code "42") (name "Net-(D2-PadA)") (class "Default")
      (node (ref "D2") (pin "A") (pinfunction "A_A") (pintype "passive"))
      (node (ref "R2") (pin "2") (pinfunction "2_2") (pintype "passive"))
    )
    (net (code "43") (name "Net-(D3-PadA)") (class "Default")
      (node (ref "D3") (pin "A") (pinfunction "A_A") (pintype "passive"))
      (node (ref "R3") (pin "2") (pinfunction "2_2") (pintype "passive"))
    )
    (net (code "44") (name "Net-(PWR-PadA)") (class "Default")
      (node (ref "PWR") (pin "A") (pinfunction "A_A") (pintype "passive"))
      (node (ref "R5") (pin "2") (pinfunction "2_2") (pintype "passive"))
    )
    (net (code "45") (name "Net-(R10-Pad1)") (class "Default")
      (node (ref "R10") (pin "1") (pinfunction "1_1") (pintype "passive"))
      (node (ref "TX") (pin "A") (pinfunction "A_A") (pintype "passive"))
    )
    (net (code "46") (name "Net-(R12-Pad1)") (class "Default")
      (node (ref "R12") (pin "1") (pinfunction "1_1") (pintype "passive"))
      (node (ref "RX") (pin "A") (pinfunction "A_A") (pintype "passive"))
    )
    (net (code "47") (name "Net-(USB-DM)") (class "Default")
      (node (ref "R7") (pin "2") (pinfunction "2_2") (pintype "passive"))
      (node (ref "USB") (pin "2") (pinfunction "DM_2") (pintype "bidirectional"))
    )
    (net (code "48") (name "Net-(USB-DP)") (class "Default")
      (node (ref "R8") (pin "2") (pinfunction "2_2") (pintype "passive"))
      (node (ref "USB") (pin "3") (pinfunction "DP_3") (pintype "bidirectional"))
    )
    (net (code "49") (name "Net-(USB-VCC)") (class "Default")
      (node (ref "F1") (pin "2") (pinfunction "2_2") (pintype "passive"))
      (node (ref "USB") (pin "1") (pinfunction "VCC_1") (pintype "passive"))
    )
    (net (code "50") (name "unconnected-(CH340C-CTS#-Pad9)") (class "Default")
      (node (ref "CH340C") (pin "9") (pinfunction "CTS#_9") (pintype "passive"))
    )
    (net (code "51") (name "unconnected-(CH340C-DCD#-Pad12)") (class "Default")
      (node (ref "CH340C") (pin "12") (pinfunction "DCD#_12") (pintype "passive"))
    )
    (net (code "52") (name "unconnected-(CH340C-DSR#-Pad10)") (class "Default")
      (node (ref "CH340C") (pin "10") (pinfunction "DSR#_10") (pintype "passive"))
    )
    (net (code "53") (name "unconnected-(CH340C-DTR#-Pad13)") (class "Default")
      (node (ref "CH340C") (pin "13") (pinfunction "DTR#_13") (pintype "passive"))
    )
    (net (code "54") (name "unconnected-(CH340C-R232-Pad15)") (class "Default")
      (node (ref "CH340C") (pin "15") (pinfunction "R232_15") (pintype "passive"))
    )
    (net (code "55") (name "unconnected-(CH340C-RI#-Pad11)") (class "Default")
      (node (ref "CH340C") (pin "11") (pinfunction "RI#_11") (pintype "passive"))
    )
    (net (code "56") (name "unconnected-(CH340C-RTS#-Pad14)") (class "Default")
      (node (ref "CH340C") (pin "14") (pinfunction "RTS#_14") (pintype "passive"))
    )
    (net (code "57") (name "unconnected-(CH340C-X1-Pad7)") (class "Default")
      (node (ref "CH340C") (pin "7") (pinfunction "X1_7") (pintype "passive"))
    )
    (net (code "58") (name "unconnected-(CH340C-X2-Pad8)") (class "Default")
      (node (ref "CH340C") (pin "8") (pinfunction "X2_8") (pintype "passive"))
    )
    (net (code "59") (name "unconnected-(P3-Pad9)") (class "Default")
      (node (ref "P3") (pin "9") (pinfunction "9_9") (pintype "passive"))
    )
    (net (code "60") (name "unconnected-(USB-ID-Pad4)") (class "Default")
      (node (ref "USB") (pin "4") (pinfunction "ID_4") (pintype "passive"))
    )
  )
)
